# Powers.net
KiCad netlist of a schematic drawn in Altium Designer
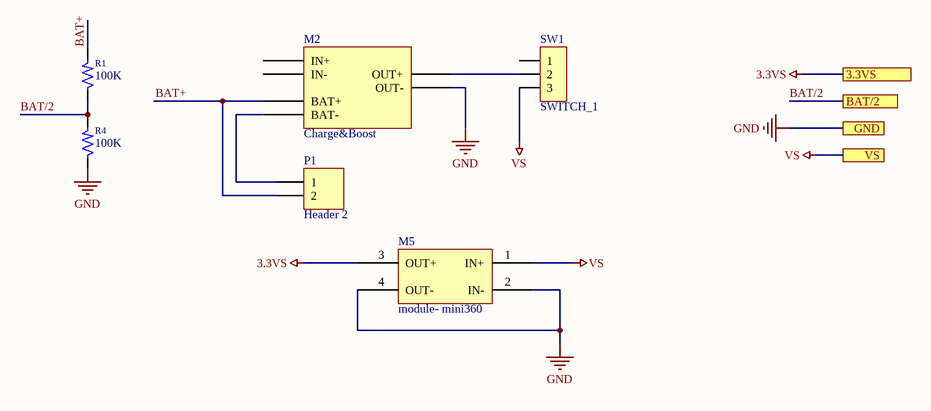
[diagram p0: Powers.SchDoc]

(export (version "E")
  (design (tool "Eeschema 10.0.6"))
  (components
    (comp (ref "M2")
      (value "Charge&Boost")
      (footprint "Charge&Boost")
      (libsource (lib "MicroMouse") (part "Charge&Boost"))
    )
    (comp (ref "M5")
      (value "module- mini360")
      (footprint "MODULE-MINI360")
      (libsource (lib "MicroMouse") (part "module- mini360"))
    )
    (comp (ref "P1")
      (value "Header 2")
      (footprint "HDR1X2")
      (description "Header, 2-Pin")
      (fields (field (name "PUBLISHER") "Altium Limited"))
      (libsource (lib "Miscellaneous Connectors") (part "Header 2"))
    )
    (comp (ref "R1")
      (value "100K")
      (footprint "RESC2012X70N")
      (description "Res 0805")
      (libsource (lib "MicroMouse") (part "Res SMD"))
    )
    (comp (ref "R4")
      (value "100K")
      (footprint "RESC2012X70N")
      (description "Res 0805")
      (libsource (lib "MicroMouse") (part "Res SMD"))
    )
    (comp (ref "SW1")
      (value "SWITCH_1")
      (footprint "SWITCH")
      (libsource (lib "MicroMouse") (part "SWITCH_1"))
    )
  )
  (nets
    (net (code "1") (name "/BAT+") (class "Default")
      (node (ref "M2") (pin "BAT+") (pinfunction "BAT+_BAT+") (pintype "passive"))
      (node (ref "P1") (pin "2") (pinfunction "2_2") (pintype "passive"))
      (node (ref "R1") (pin "2") (pinfunction "2_2") (pintype "passive"))
    )
    (net (code "2") (name "/BAT{slash}2") (class "Default")
      (node (ref "R1") (pin "1") (pinfunction "1_1") (pintype "passive"))
      (node (ref "R4") (pin "2") (pinfunction "2_2") (pintype "passive"))
    )
    (net (code "3") (name "3.3VS") (class "Default")
      (node (ref "M5") (pin "3") (pinfunction "OUT+_3") (pintype "passive"))
    )
    (net (code "4") (name "GND") (class "Default")
      (node (ref "M2") (pin "OUT-") (pinfunction "OUT-_OUT-") (pintype "passive"))
      (node (ref "M5") (pin "2") (pinfunction "IN-_2") (pintype "passive"))
      (node (ref "M5") (pin "4") (pinfunction "OUT-_4") (pintype "passive"))
      (node (ref "R4") (pin "1") (pinfunction "1_1") (pintype "passive"))
    )
    (net (code "5") (name "Net-(M2-PadBAT-)") (class "Default")
      (node (ref "M2") (pin "BAT-") (pinfunction "BAT-_BAT-") (pintype "passive"))
      (node (ref "P1") (pin "1") (pinfunction "1_1") (pintype "passive"))
    )
    (net (code "6") (name "Net-(M2-PadOUT+)") (class "Default")
      (node (ref "M2") (pin "OUT+") (pinfunction "OUT+_OUT+") (pintype "passive"))
      (node (ref "SW1") (pin "2") (pinfunction "2_2") (pintype "passive"))
    )
    (net (code "7") (name "VS") (class "Default")
      (node (ref "M5") (pin "1") (pinfunction "IN+_1") (pintype "passive"))
      (node (ref "SW1") (pin "3") (pinfunction "3_3") (pintype "passive"))
    )
    (net (code "8") (name "unconnected-(M2-PadIN+)") (class "Default")
      (node (ref "M2") (pin "IN+") (pinfunction "IN+_IN+") (pintype "passive"))
    )
    (net (code "9") (name "unconnected-(M2-PadIN-)") (class "Default")
      (node (ref "M2") (pin "IN-") (pinfunction "IN-_IN-") (pintype "passive"))
    )
    (net (code "10") (name "unconnected-(SW1-Pad1)") (class "Default")
      (node (ref "SW1") (pin "1") (pinfunction "1_1") (pintype "passive"))
    )
  )
)
